# schema.net
KiCad netlist of a schematic drawn in Altium Designer
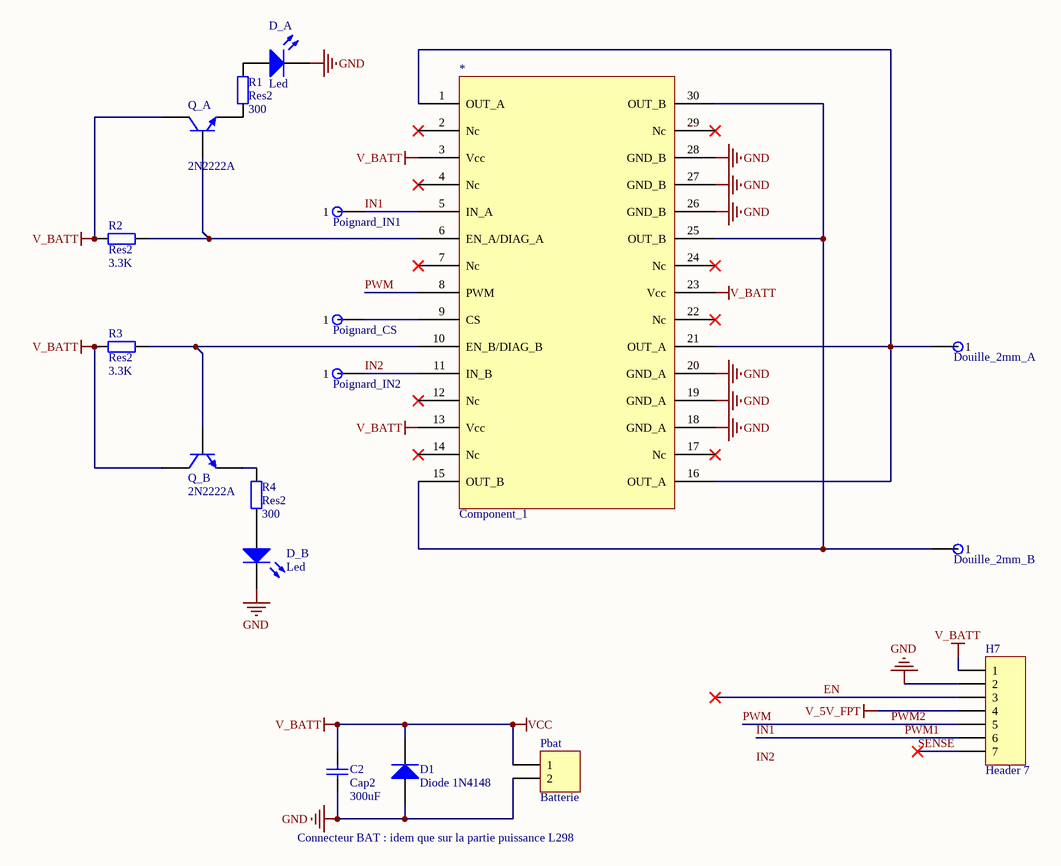
[diagram p0: schema.SchDoc]

(export (version "E")
  (design (tool "Eeschema 10.0.6"))
  (components
    (comp (ref "*")
      (value "Component_1")
      (footprint "MultiPowerSO-30")
      (libsource (lib "VNH3SP30-E") (part "Component_1"))
    )
    (comp (ref "C2")
      (value "Cap2")
      (footprint "CAPA2")
      (description "Capacitor")
      (fields (field (name "ALTIUM_VALUE") "300uF") (field (name "PUBLISHER") "Altium Limited"))
      (libsource (lib "LIBRAIRIE_INTEGREE_PHELMA1") (part "Cap2"))
    )
    (comp (ref "D1")
      (value "Diode 1N4148")
      (footprint "Ddiode")
      (description "High Conductance Fast Diode")
      (fields (field (name "PUBLISHER") "Altium Limited"))
      (libsource (lib "LIBRAIRIE_INTEGREE_PHELMA1") (part "Diode 1N4148"))
    )
    (comp (ref "Douille_2mm_A")
      (value "douille_2mm")
      (footprint "Douille-2mm")
      (description "1-Pin")
      (fields (field (name "PUBLISHER") "Altium Limited"))
      (libsource (lib "INTEGRATED_LIBRARY1_CONNECTEURS") (part "douille_2mm"))
    )
    (comp (ref "Douille_2mm_B")
      (value "douille_2mm")
      (footprint "Douille-2mm")
      (description "1-Pin")
      (fields (field (name "PUBLISHER") "Altium Limited"))
      (libsource (lib "INTEGRATED_LIBRARY1_CONNECTEURS") (part "douille_2mm"))
    )
    (comp (ref "D_A")
      (value "Led")
      (footprint "LED")
      (description "LED")
      (fields (field (name "PUBLISHER") "Altium Limited"))
      (libsource (lib "LIBRAIRIE_INTEGREE_PHELMA1") (part "Led"))
    )
    (comp (ref "D_B")
      (value "Led")
      (footprint "LED")
      (description "LED")
      (fields (field (name "PUBLISHER") "Altium Limited"))
      (libsource (lib "LIBRAIRIE_INTEGREE_PHELMA1") (part "Led"))
    )
    (comp (ref "H7")
      (value "Header 7")
      (footprint "HDR1X7")
      (description "Header, 7-Pin")
      (fields (field (name "PUBLISHER") "Altium Limited"))
      (libsource (lib "Miscellaneous Connectors") (part "Header 7"))
    )
    (comp (ref "Pbat")
      (value "Batterie")
      (footprint "Bornier_2")
      (description "Header, 2-Pin")
      (fields (field (name "PUBLISHER") "Altium Limited"))
      (libsource (lib "INTEGRATED_LIBRARY1_CONNECTEURS") (part "Bornier_2"))
    )
    (comp (ref "Poignard_CS")
      (value "Poignard")
      (footprint "Poignard")
      (fields (field (name "PUBLISHER") "Altium Limited"))
      (libsource (lib "INTEGRATED_LIBRARY1_CONNECTEURS") (part "Poignard"))
    )
    (comp (ref "Poignard_IN1")
      (value "Poignard")
      (footprint "Poignard")
      (fields (field (name "PUBLISHER") "Altium Limited"))
      (libsource (lib "INTEGRATED_LIBRARY1_CONNECTEURS") (part "Poignard"))
    )
    (comp (ref "Poignard_IN2")
      (value "Poignard")
      (footprint "Poignard")
      (fields (field (name "PUBLISHER") "Altium Limited"))
      (libsource (lib "INTEGRATED_LIBRARY1_CONNECTEURS") (part "Poignard"))
    )
    (comp (ref "Q_A")
      (value "2N2222A")
      (footprint "TO-18")
      (description "High Speed Switches")
      (fields (field (name "PUBLISHER") "Altium Limited"))
      (libsource (lib "LIBRAIRIE_INTEGREE_PHELMA1") (part "2N2222A"))
    )
    (comp (ref "Q_B")
      (value "2N2222A")
      (footprint "TO-18")
      (description "High Speed Switches")
      (fields (field (name "PUBLISHER") "Altium Limited"))
      (libsource (lib "LIBRAIRIE_INTEGREE_PHELMA1") (part "2N2222A"))
    )
    (comp (ref "R1")
      (value "Res2")
      (footprint "res5_1/4W")
      (description "Resistor")
      (fields (field (name "ALTIUM_VALUE") "300") (field (name "PUBLISHER") "Altium Limited"))
      (libsource (lib "") (part "Res2_2"))
    )
    (comp (ref "R2")
      (value "Res2")
      (footprint "res5_1/4W")
      (description "Resistor")
      (fields (field (name "ALTIUM_VALUE") "3.3K") (field (name "PUBLISHER") "Altium Limited"))
      (libsource (lib "LIBRAIRIE_INTEGREE_PHELMA1") (part "Res2"))
    )
    (comp (ref "R3")
      (value "Res2")
      (footprint "res5_1/4W")
      (description "Resistor")
      (fields (field (name "ALTIUM_VALUE") "3.3K") (field (name "PUBLISHER") "Altium Limited"))
      (libsource (lib "LIBRAIRIE_INTEGREE_PHELMA1") (part "Res2"))
    )
    (comp (ref "R4")
      (value "Res2")
      (footprint "res5_1/4W")
      (description "Resistor")
      (fields (field (name "ALTIUM_VALUE") "300") (field (name "PUBLISHER") "Altium Limited"))
      (libsource (lib "") (part "Res2_1"))
    )
  )
  (nets
    (net (code "1") (name "/EN") (class "Default")
      (node (ref "H7") (pin "3") (pinfunction "3_3") (pintype "passive+no_connect"))
    )
    (net (code "2") (name "/IN1") (class "Default")
      (node (ref "*") (pin "5") (pinfunction "IN_A_5") (pintype "passive"))
      (node (ref "H7") (pin "6") (pinfunction "6_6") (pintype "passive"))
      (node (ref "Poignard_IN1") (pin "1") (pinfunction "1_1") (pintype "passive"))
    )
    (net (code "3") (name "/IN2") (class "Default")
      (node (ref "*") (pin "11") (pinfunction "IN_B_11") (pintype "passive"))
      (node (ref "Poignard_IN2") (pin "1") (pinfunction "1_1") (pintype "passive"))
    )
    (net (code "4") (name "/PWM") (class "Default")
      (node (ref "*") (pin "8") (pinfunction "PWM_8") (pintype "passive"))
      (node (ref "H7") (pin "5") (pinfunction "5_5") (pintype "passive"))
    )
    (net (code "5") (name "/SENSE") (class "Default")
      (node (ref "H7") (pin "7") (pinfunction "7_7") (pintype "passive+no_connect"))
    )
    (net (code "6") (name "GND") (class "Default")
      (node (ref "*") (pin "18") (pinfunction "GND_A_18") (pintype "passive"))
      (node (ref "*") (pin "19") (pinfunction "GND_A_19") (pintype "passive"))
      (node (ref "*") (pin "20") (pinfunction "GND_A_20") (pintype "passive"))
      (node (ref "*") (pin "26") (pinfunction "GND_B_26") (pintype "passive"))
      (node (ref "*") (pin "27") (pinfunction "GND_B_27") (pintype "passive"))
      (node (ref "*") (pin "28") (pinfunction "GND_B_28") (pintype "passive"))
      (node (ref "C2") (pin "1") (pinfunction "1_1") (pintype "passive"))
      (node (ref "D1") (pin "1") (pinfunction "A_1") (pintype "passive"))
      (node (ref "D_A") (pin "2") (pinfunction "K_2") (pintype "passive"))
      (node (ref "D_B") (pin "2") (pinfunction "K_2") (pintype "passive"))
      (node (ref "H7") (pin "2") (pinfunction "2_2") (pintype "passive"))
      (node (ref "Pbat") (pin "2") (pinfunction "2_2") (pintype "passive"))
    )
    (net (code "7") (name "Net-(*-CS)") (class "Default")
      (node (ref "*") (pin "9") (pinfunction "CS_9") (pintype "passive"))
      (node (ref "Poignard_CS") (pin "1") (pinfunction "1_1") (pintype "passive"))
    )
    (net (code "8") (name "Net-(*-EN_A{slash}DIAG_A)") (class "Default")
      (node (ref "*") (pin "6") (pinfunction "EN_A/DIAG_A_6") (pintype "passive"))
      (node (ref "Q_A") (pin "1") (pinfunction "B_1") (pintype "passive"))
      (node (ref "R2") (pin "2") (pinfunction "2_2") (pintype "passive"))
    )
    (net (code "9") (name "Net-(*-EN_B{slash}DIAG_B)") (class "Default")
      (node (ref "*") (pin "10") (pinfunction "EN_B/DIAG_B_10") (pintype "passive"))
      (node (ref "Q_B") (pin "1") (pinfunction "B_1") (pintype "passive"))
      (node (ref "R3") (pin "2") (pinfunction "2_2") (pintype "passive"))
    )
    (net (code "10") (name "Net-(*-OUT_A-Pad1)") (class "Default")
      (node (ref "*") (pin "1") (pinfunction "OUT_A_1") (pintype "passive"))
      (node (ref "*") (pin "16") (pinfunction "OUT_A_16") (pintype "passive"))
      (node (ref "*") (pin "21") (pinfunction "OUT_A_21") (pintype "passive"))
      (node (ref "Douille_2mm_A") (pin "1") (pinfunction "1_1") (pintype "passive"))
    )
    (net (code "11") (name "Net-(*-OUT_B-Pad15)") (class "Default")
      (node (ref "*") (pin "15") (pinfunction "OUT_B_15") (pintype "passive"))
      (node (ref "*") (pin "25") (pinfunction "OUT_B_25") (pintype "passive"))
      (node (ref "*") (pin "30") (pinfunction "OUT_B_30") (pintype "passive"))
      (node (ref "Douille_2mm_B") (pin "1") (pinfunction "1_1") (pintype "passive"))
    )
    (net (code "12") (name "Net-(D_A-A)") (class "Default")
      (node (ref "D_A") (pin "1") (pinfunction "A_1") (pintype "passive"))
      (node (ref "R1") (pin "2") (pinfunction "2_2") (pintype "passive"))
    )
    (net (code "13") (name "Net-(D_B-A)") (class "Default")
      (node (ref "D_B") (pin "1") (pinfunction "A_1") (pintype "passive"))
      (node (ref "R4") (pin "2") (pinfunction "2_2") (pintype "passive"))
    )
    (net (code "14") (name "Net-(Q_A-E)") (class "Default")
      (node (ref "Q_A") (pin "3") (pinfunction "E_3") (pintype "passive"))
      (node (ref "R1") (pin "1") (pinfunction "1_1") (pintype "passive"))
    )
    (net (code "15") (name "Net-(Q_B-E)") (class "Default")
      (node (ref "Q_B") (pin "3") (pinfunction "E_3") (pintype "passive"))
      (node (ref "R4") (pin "1") (pinfunction "1_1") (pintype "passive"))
    )
    (net (code "16") (name "VCC") (class "Default")
      (node (ref "*") (pin "13") (pinfunction "Vcc_13") (pintype "passive"))
      (node (ref "*") (pin "23") (pinfunction "Vcc_23") (pintype "passive"))
      (node (ref "*") (pin "3") (pinfunction "Vcc_3") (pintype "passive"))
      (node (ref "C2") (pin "2") (pinfunction "2_2") (pintype "passive"))
      (node (ref "D1") (pin "2") (pinfunction "K_2") (pintype "passive"))
      (node (ref "H7") (pin "1") (pinfunction "1_1") (pintype "passive"))
      (node (ref "Pbat") (pin "1") (pinfunction "1_1") (pintype "passive"))
      (node (ref "Q_A") (pin "2") (pinfunction "C_2") (pintype "passive"))
      (node (ref "Q_B") (pin "2") (pinfunction "C_2") (pintype "passive"))
      (node (ref "R2") (pin "1") (pinfunction "1_1") (pintype "passive"))
      (node (ref "R3") (pin "1") (pinfunction "1_1") (pintype "passive"))
    )
    (net (code "17") (name "V_5V_FPT") (class "Default")
      (node (ref "H7") (pin "4") (pinfunction "4_4") (pintype "passive"))
    )
    (net (code "18") (name "unconnected-(*-Nc-Pad2)") (class "Default")
      (node (ref "*") (pin "2") (pinfunction "Nc_2") (pintype "passive+no_connect"))
    )
    (net (code "19") (name "unconnected-(*-Nc-Pad4)") (class "Default")
      (node (ref "*") (pin "4") (pinfunction "Nc_4") (pintype "passive+no_connect"))
    )
    (net (code "20") (name "unconnected-(*-Nc-Pad7)") (class "Default")
      (node (ref "*") (pin "7") (pinfunction "Nc_7") (pintype "passive+no_connect"))
    )
    (net (code "21") (name "unconnected-(*-Nc-Pad12)") (class "Default")
      (node (ref "*") (pin "12") (pinfunction "Nc_12") (pintype "passive+no_connect"))
    )
    (net (code "22") (name "unconnected-(*-Nc-Pad14)") (class "Default")
      (node (ref "*") (pin "14") (pinfunction "Nc_14") (pintype "passive+no_connect"))
    )
    (net (code "23") (name "unconnected-(*-Nc-Pad17)") (class "Default")
      (node (ref "*") (pin "17") (pinfunction "Nc_17") (pintype "passive+no_connect"))
    )
    (net (code "24") (name "unconnected-(*-Nc-Pad22)") (class "Default")
      (node (ref "*") (pin "22") (pinfunction "Nc_22") (pintype "passive+no_connect"))
    )
    (net (code "25") (name "unconnected-(*-Nc-Pad24)") (class "Default")
      (node (ref "*") (pin "24") (pinfunction "Nc_24") (pintype "passive+no_connect"))
    )
    (net (code "26") (name "unconnected-(*-Nc-Pad29)") (class "Default")
      (node (ref "*") (pin "29") (pinfunction "Nc_29") (pintype "passive+no_connect"))
    )
  )
)
